# SCH_signal_16_2024-04-10.net
KiCad netlist of a schematic drawn in EasyEDA
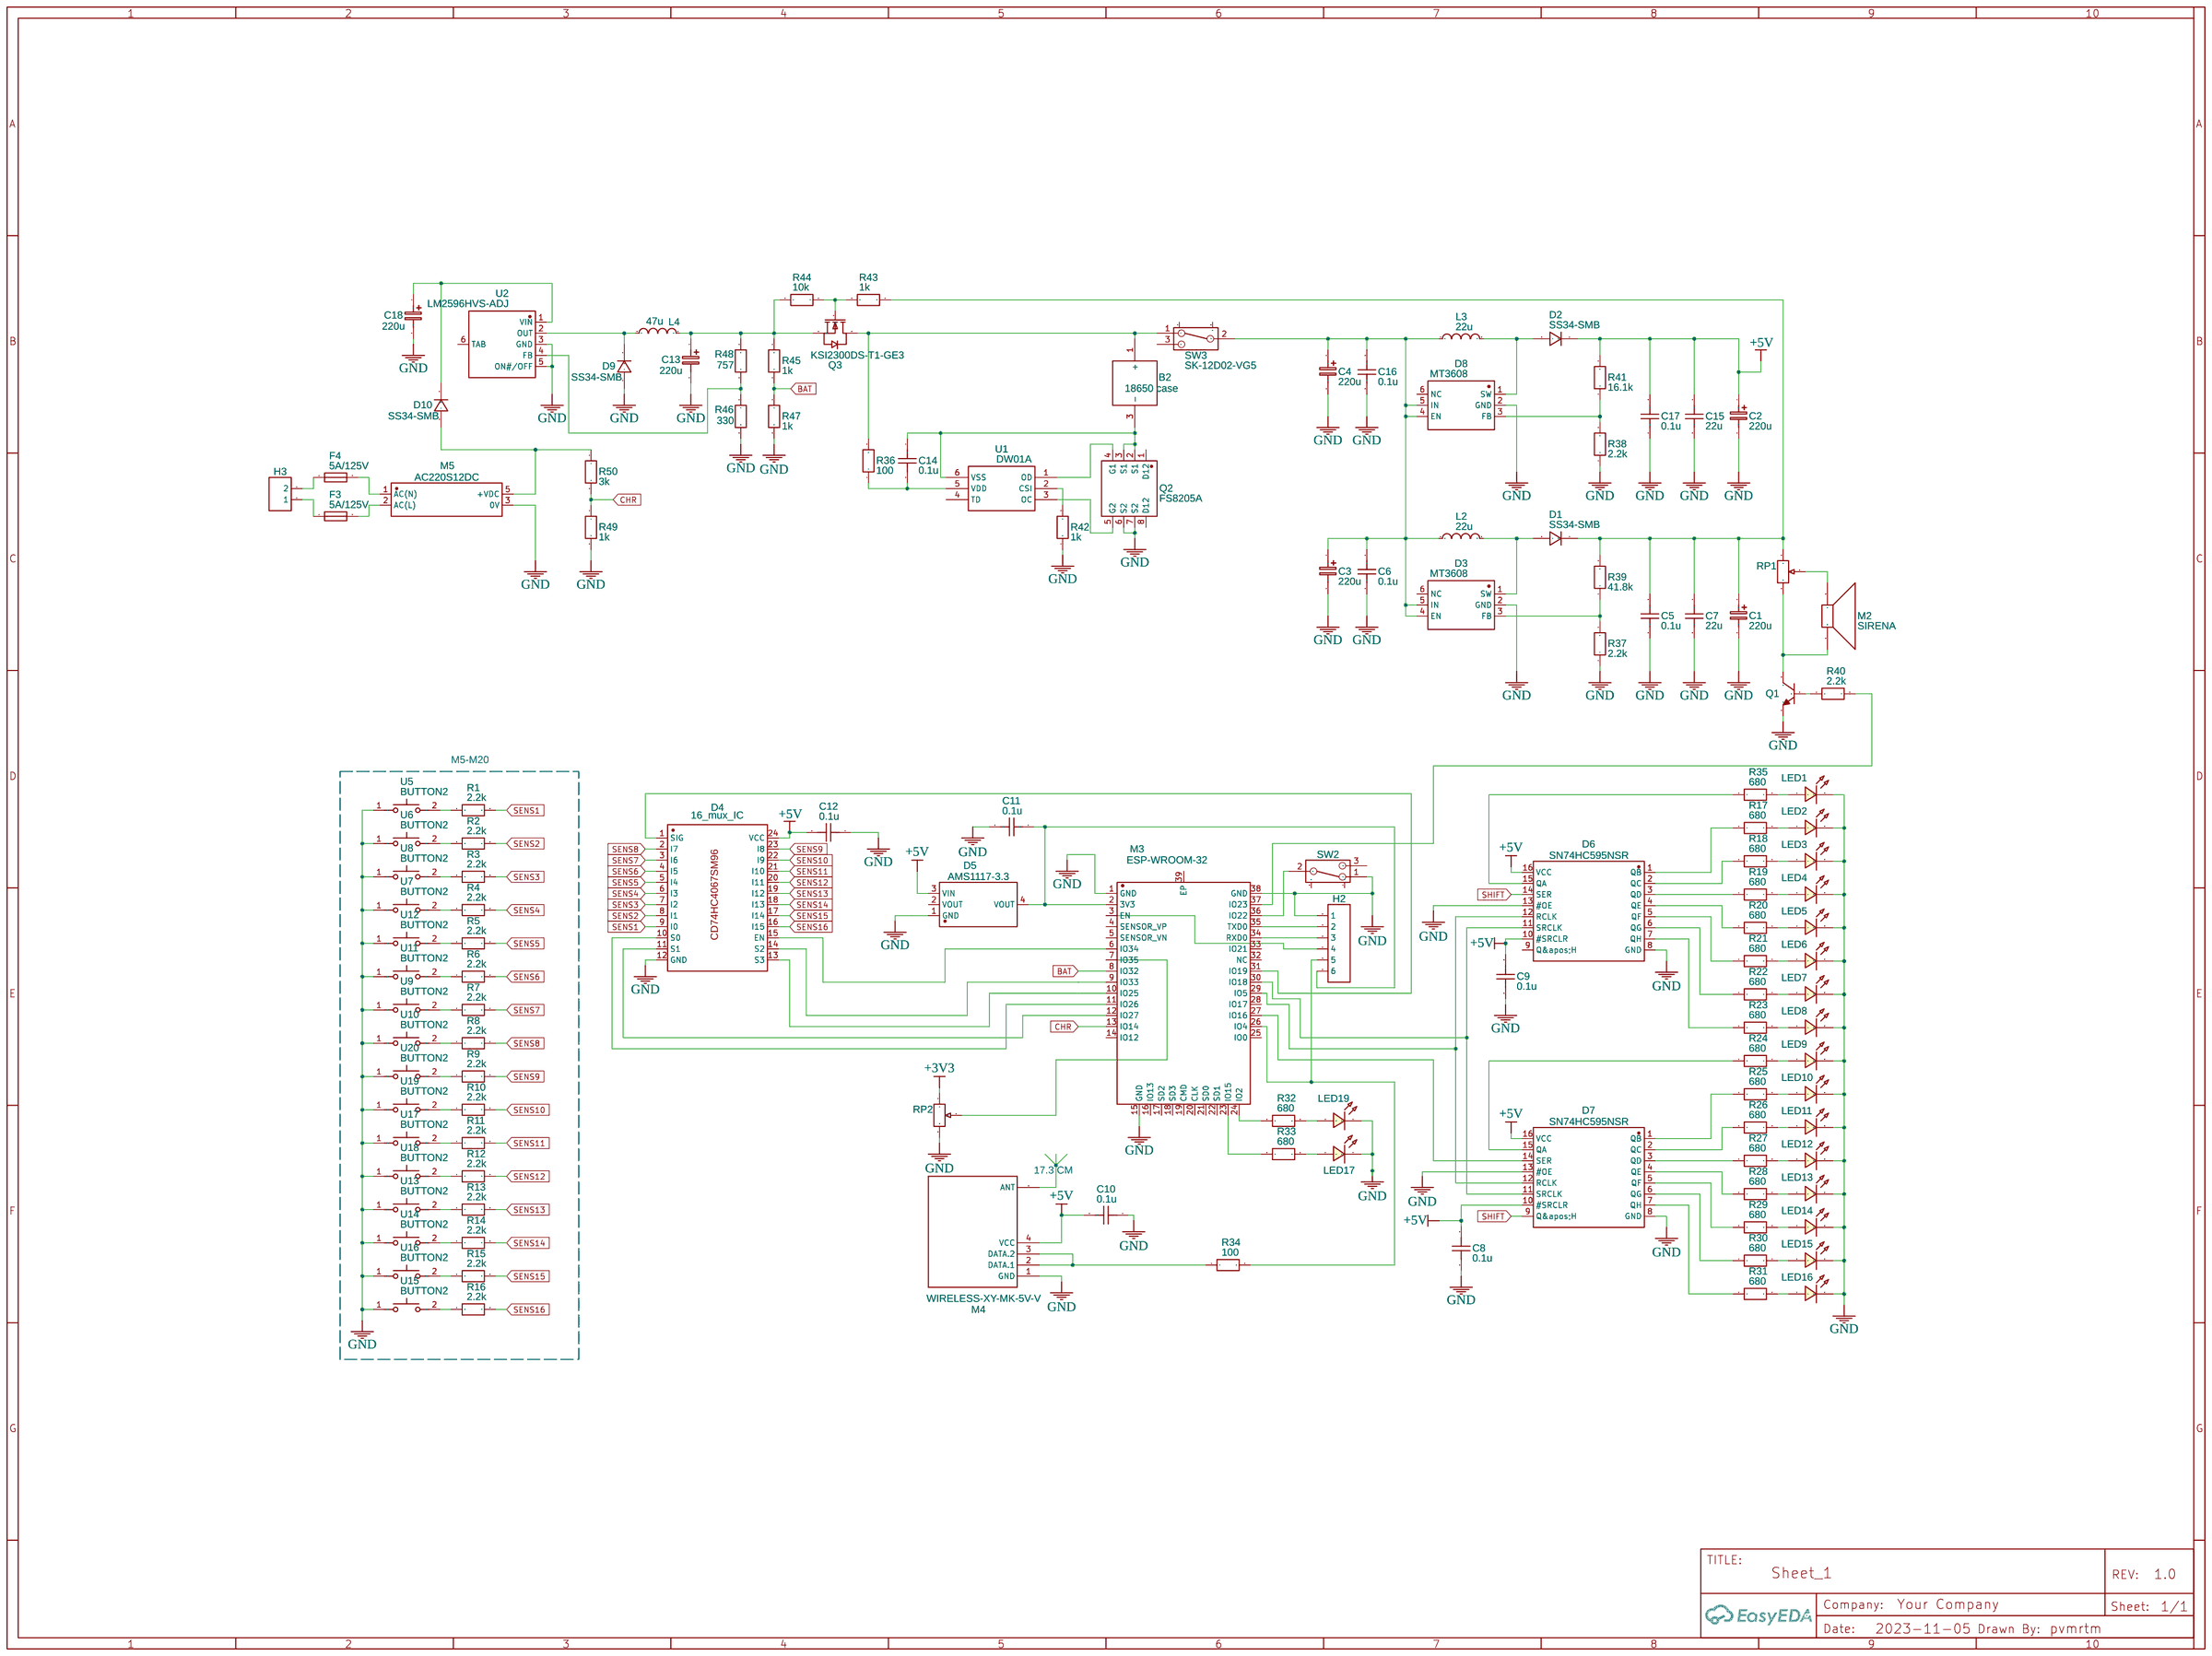
[diagram p0: schematic sheet]

(export (version "E")
  (design (tool "Eeschema 10.0.6"))
  (components
    (comp (ref "B2") (value "18650 case") (libsource (lib "") (part "18650 case")))
    (comp (ref "C1") (value "220u") (libsource (lib "") (part "CE_SMD_D8.0×H10.5_EU_1")))
    (comp (ref "C2") (value "220u") (libsource (lib "") (part "CE_SMD_D8.0×H10.5_EU_3")))
    (comp (ref "C3") (value "220u") (libsource (lib "") (part "CE_SMD_D8.0×H10.5_EU_1")))
    (comp (ref "C4") (value "220u") (libsource (lib "") (part "CE_SMD_D8.0×H10.5_EU_3")))
    (comp (ref "C5") (value "0.1u") (libsource (lib "") (part "C_0603_US")))
    (comp (ref "C6") (value "0.1u") (libsource (lib "") (part "C_0603_US")))
    (comp (ref "C7") (value "22u") (libsource (lib "") (part "C_0603_US_1")))
    (comp (ref "C8") (value "0.1u") (libsource (lib "") (part "C_0603_US")))
    (comp (ref "C9") (value "0.1u") (libsource (lib "") (part "C_0603_US")))
    (comp (ref "C10") (value "0.1u") (libsource (lib "") (part "C_0603_US_2")))
    (comp (ref "C11") (value "0.1u") (libsource (lib "") (part "C_0603_US_2")))
    (comp (ref "C12") (value "0.1u") (libsource (lib "") (part "C_0603_US_2")))
    (comp (ref "C13") (value "220u") (libsource (lib "") (part "CE_SMD_D8.0×H10.5_EU_2")))
    (comp (ref "C14") (value "0.1u") (libsource (lib "") (part "C_0603_US_1")))
    (comp (ref "C15") (value "22u") (libsource (lib "") (part "C_0603_US_1")))
    (comp (ref "C16") (value "0.1u") (libsource (lib "") (part "C_0603_US")))
    (comp (ref "C17") (value "0.1u") (libsource (lib "") (part "C_0603_US")))
    (comp (ref "C18") (value "220u") (libsource (lib "") (part "CE_SMD_D8.0×H10.5_EU")))
    (comp (ref "D1")
      (value "SS34-SMB")
      (fields (field (name "Manufacturer") "GOODWORK(固得沃克)"))
      (libsource (lib "") (part "SS34-SMB"))
    )
    (comp (ref "D2")
      (value "SS34-SMB")
      (fields (field (name "Manufacturer") "GOODWORK(固得沃克)"))
      (libsource (lib "") (part "SS34-SMB"))
    )
    (comp (ref "D3")
      (value "MT3608")
      (fields (field (name "Manufacturer") "西安航天民芯"))
      (libsource (lib "") (part "MT3608"))
    )
    (comp (ref "D4") (value "16_mux_IC") (libsource (lib "") (part "16_mux_IC")))
    (comp (ref "D5")
      (value "AMS1117-3.3")
      (fields (field (name "Manufacturer") "AMS"))
      (libsource (lib "") (part "AMS1117-3.3"))
    )
    (comp (ref "D6")
      (value "SN74HC595NSR")
      (fields (field (name "Manufacturer") "TI(德州仪器)"))
      (libsource (lib "") (part "SN74HC595NSR"))
    )
    (comp (ref "D7")
      (value "SN74HC595NSR")
      (fields (field (name "Manufacturer") "TI(德州仪器)"))
      (libsource (lib "") (part "SN74HC595NSR"))
    )
    (comp (ref "D8")
      (value "MT3608")
      (fields (field (name "Manufacturer") "西安航天民芯"))
      (libsource (lib "") (part "MT3608"))
    )
    (comp (ref "D9")
      (value "SS34-SMB")
      (fields (field (name "Manufacturer") "GOODWORK(固得沃克)"))
      (libsource (lib "") (part "SS34-SMB_1"))
    )
    (comp (ref "D10")
      (value "SS34-SMB")
      (fields (field (name "Manufacturer") "GOODWORK(固得沃克)"))
      (libsource (lib "") (part "SS34-SMB_1"))
    )
    (comp (ref "F3") (value "5A/125V") (libsource (lib "") (part "5A/125V")))
    (comp (ref "F4") (value "5A/125V") (libsource (lib "") (part "5A/125V")))
    (comp (ref "H2") (value "HDR-F-2.54_1x6") (libsource (lib "") (part "HDR-F-2.54_1x6")))
    (comp (ref "H3") (value "HDR-F-2.54_1x2") (libsource (lib "") (part "HDR-F-2.54_1x2")))
    (comp (ref "L2") (value "22u") (libsource (lib "") (part "L_AXIAL-0.6_US")))
    (comp (ref "L3") (value "22u") (libsource (lib "") (part "L_AXIAL-0.6_US")))
    (comp (ref "L4") (value "47u") (libsource (lib "") (part "L_AXIAL-0.6_US_1")))
    (comp (ref "LED1")
      (value "LED-TH-5mm_R")
      (fields
        (field (name "Manufacturer Part") "333-2SURD/S530-A3")
        (field (name "Manufacturer") "EVERLIGHT(台湾亿光)")
      )
      (libsource (lib "") (part "LED-TH-5mm_R"))
    )
    (comp (ref "LED2")
      (value "LED-TH-5mm_R")
      (fields
        (field (name "Manufacturer Part") "333-2SURD/S530-A3")
        (field (name "Manufacturer") "EVERLIGHT(台湾亿光)")
      )
      (libsource (lib "") (part "LED-TH-5mm_R"))
    )
    (comp (ref "LED3")
      (value "LED-TH-5mm_R")
      (fields
        (field (name "Manufacturer Part") "333-2SURD/S530-A3")
        (field (name "Manufacturer") "EVERLIGHT(台湾亿光)")
      )
      (libsource (lib "") (part "LED-TH-5mm_R"))
    )
    (comp (ref "LED4")
      (value "LED-TH-5mm_R")
      (fields
        (field (name "Manufacturer Part") "333-2SURD/S530-A3")
        (field (name "Manufacturer") "EVERLIGHT(台湾亿光)")
      )
      (libsource (lib "") (part "LED-TH-5mm_R"))
    )
    (comp (ref "LED5")
      (value "LED-TH-5mm_R")
      (fields
        (field (name "Manufacturer Part") "333-2SURD/S530-A3")
        (field (name "Manufacturer") "EVERLIGHT(台湾亿光)")
      )
      (libsource (lib "") (part "LED-TH-5mm_R"))
    )
    (comp (ref "LED6")
      (value "LED-TH-5mm_R")
      (fields
        (field (name "Manufacturer Part") "333-2SURD/S530-A3")
        (field (name "Manufacturer") "EVERLIGHT(台湾亿光)")
      )
      (libsource (lib "") (part "LED-TH-5mm_R"))
    )
    (comp (ref "LED7")
      (value "LED-TH-5mm_R")
      (fields
        (field (name "Manufacturer Part") "333-2SURD/S530-A3")
        (field (name "Manufacturer") "EVERLIGHT(台湾亿光)")
      )
      (libsource (lib "") (part "LED-TH-5mm_R"))
    )
    (comp (ref "LED8")
      (value "LED-TH-5mm_R")
      (fields
        (field (name "Manufacturer Part") "333-2SURD/S530-A3")
        (field (name "Manufacturer") "EVERLIGHT(台湾亿光)")
      )
      (libsource (lib "") (part "LED-TH-5mm_R"))
    )
    (comp (ref "LED9")
      (value "LED-TH-5mm_R")
      (fields
        (field (name "Manufacturer Part") "333-2SURD/S530-A3")
        (field (name "Manufacturer") "EVERLIGHT(台湾亿光)")
      )
      (libsource (lib "") (part "LED-TH-5mm_R"))
    )
    (comp (ref "LED10")
      (value "LED-TH-5mm_R")
      (fields
        (field (name "Manufacturer Part") "333-2SURD/S530-A3")
        (field (name "Manufacturer") "EVERLIGHT(台湾亿光)")
      )
      (libsource (lib "") (part "LED-TH-5mm_R"))
    )
    (comp (ref "LED11")
      (value "LED-TH-5mm_R")
      (fields
        (field (name "Manufacturer Part") "333-2SURD/S530-A3")
        (field (name "Manufacturer") "EVERLIGHT(台湾亿光)")
      )
      (libsource (lib "") (part "LED-TH-5mm_R"))
    )
    (comp (ref "LED12")
      (value "LED-TH-5mm_R")
      (fields
        (field (name "Manufacturer Part") "333-2SURD/S530-A3")
        (field (name "Manufacturer") "EVERLIGHT(台湾亿光)")
      )
      (libsource (lib "") (part "LED-TH-5mm_R"))
    )
    (comp (ref "LED13")
      (value "LED-TH-5mm_R")
      (fields
        (field (name "Manufacturer Part") "333-2SURD/S530-A3")
        (field (name "Manufacturer") "EVERLIGHT(台湾亿光)")
      )
      (libsource (lib "") (part "LED-TH-5mm_R"))
    )
    (comp (ref "LED14")
      (value "LED-TH-5mm_R")
      (fields
        (field (name "Manufacturer Part") "333-2SURD/S530-A3")
        (field (name "Manufacturer") "EVERLIGHT(台湾亿光)")
      )
      (libsource (lib "") (part "LED-TH-5mm_R"))
    )
    (comp (ref "LED15")
      (value "LED-TH-5mm_R")
      (fields
        (field (name "Manufacturer Part") "333-2SURD/S530-A3")
        (field (name "Manufacturer") "EVERLIGHT(台湾亿光)")
      )
      (libsource (lib "") (part "LED-TH-5mm_R"))
    )
    (comp (ref "LED16")
      (value "LED-TH-5mm_R")
      (fields
        (field (name "Manufacturer Part") "333-2SURD/S530-A3")
        (field (name "Manufacturer") "EVERLIGHT(台湾亿光)")
      )
      (libsource (lib "") (part "LED-TH-5mm_R"))
    )
    (comp (ref "LED17")
      (value "LED-TH-5mm_G")
      (fields
        (field (name "Manufacturer Part") "333-2SYGD/S530-E2")
        (field (name "Manufacturer") "EVERLIGHT(台湾亿光)")
      )
      (libsource (lib "") (part "LED-TH-5mm_G"))
    )
    (comp (ref "LED19") (value "LED-TH-5mm_B") (libsource (lib "") (part "LED-TH-5mm_B")))
    (comp (ref "M2") (value "SIRENA") (libsource (lib "") (part "SIRENA SIMBOL")))
    (comp (ref "M3")
      (value "ESP-WROOM-32")
      (fields
        (field (name "Manufacturer Part") "ESP32-WROOM-32")
        (field (name "Manufacturer") "ESPRESSIF(乐鑫)")
      )
      (libsource (lib "") (part "ESP-WROOM-32"))
    )
    (comp (ref "M4") (value "WIRELESS-XY-MK-5V-V") (libsource (lib "") (part "WIRELESS-XY-MK-5V-V")))
    (comp (ref "M5")
      (value "AC220S12DC")
      (fields (field (name "Manufacturer Part") "AC220S12DC-3W") (field (name "Manufacturer") "HenLv(恒率)"))
      (libsource (lib "") (part "AC220S12DC-3W_C348883"))
    )
    (comp (ref "Q1")
      (value "2N3904(SOT-23)")
      (fields (field (name "Manufacturer Part") "2n3904S-RTK/PS") (field (name "Manufacturer") "KEC"))
      (libsource (lib "") (part "2N3904(SOT-23)"))
    )
    (comp (ref "Q2")
      (value "FS8205A")
      (fields (field (name "Manufacturer") "FORTUNE(富晶)"))
      (libsource (lib "") (part "FS8205A"))
    )
    (comp (ref "Q3")
      (value "KSI2300DS-T1-GE3")
      (fields (field (name "Manufacturer") "KUU"))
      (libsource (lib "") (part "KSI2300DS-T1-GE3"))
    )
    (comp (ref "R1") (value "2.2k") (libsource (lib "") (part "R_AXIAL-0.8_EU")))
    (comp (ref "R2") (value "2.2k") (libsource (lib "") (part "R_AXIAL-0.8_EU")))
    (comp (ref "R3") (value "2.2k") (libsource (lib "") (part "R_AXIAL-0.8_EU")))
    (comp (ref "R4") (value "2.2k") (libsource (lib "") (part "R_AXIAL-0.8_EU")))
    (comp (ref "R5") (value "2.2k") (libsource (lib "") (part "R_AXIAL-0.8_EU")))
    (comp (ref "R6") (value "2.2k") (libsource (lib "") (part "R_AXIAL-0.8_EU")))
    (comp (ref "R7") (value "2.2k") (libsource (lib "") (part "R_AXIAL-0.8_EU")))
    (comp (ref "R8") (value "2.2k") (libsource (lib "") (part "R_AXIAL-0.8_EU")))
    (comp (ref "R9") (value "2.2k") (libsource (lib "") (part "R_AXIAL-0.8_EU")))
    (comp (ref "R10") (value "2.2k") (libsource (lib "") (part "R_AXIAL-0.8_EU")))
    (comp (ref "R11") (value "2.2k") (libsource (lib "") (part "R_AXIAL-0.8_EU")))
    (comp (ref "R12") (value "2.2k") (libsource (lib "") (part "R_AXIAL-0.8_EU")))
    (comp (ref "R13") (value "2.2k") (libsource (lib "") (part "R_AXIAL-0.8_EU")))
    (comp (ref "R14") (value "2.2k") (libsource (lib "") (part "R_AXIAL-0.8_EU")))
    (comp (ref "R15") (value "2.2k") (libsource (lib "") (part "R_AXIAL-0.8_EU")))
    (comp (ref "R16") (value "2.2k") (libsource (lib "") (part "R_AXIAL-0.8_EU")))
    (comp (ref "R17") (value "680") (libsource (lib "") (part "R_1206_EU_1")))
    (comp (ref "R18") (value "680") (libsource (lib "") (part "R_1206_EU_1")))
    (comp (ref "R19") (value "680") (libsource (lib "") (part "R_1206_EU_1")))
    (comp (ref "R20") (value "680") (libsource (lib "") (part "R_1206_EU_1")))
    (comp (ref "R21") (value "680") (libsource (lib "") (part "R_1206_EU_1")))
    (comp (ref "R22") (value "680") (libsource (lib "") (part "R_1206_EU_1")))
    (comp (ref "R23") (value "680") (libsource (lib "") (part "R_1206_EU_1")))
    (comp (ref "R24") (value "680") (libsource (lib "") (part "R_1206_EU_1")))
    (comp (ref "R25") (value "680") (libsource (lib "") (part "R_1206_EU_1")))
    (comp (ref "R26") (value "680") (libsource (lib "") (part "R_1206_EU_1")))
    (comp (ref "R27") (value "680") (libsource (lib "") (part "R_1206_EU_1")))
    (comp (ref "R28") (value "680") (libsource (lib "") (part "R_1206_EU_1")))
    (comp (ref "R29") (value "680") (libsource (lib "") (part "R_1206_EU_1")))
    (comp (ref "R30") (value "680") (libsource (lib "") (part "R_1206_EU_1")))
    (comp (ref "R31") (value "680") (libsource (lib "") (part "R_1206_EU_1")))
    (comp (ref "R32") (value "680") (libsource (lib "") (part "R_1206_EU_1")))
    (comp (ref "R33") (value "680") (libsource (lib "") (part "R_1206_EU_1")))
    (comp (ref "R34") (value "100") (libsource (lib "") (part "R_1206_EU_1")))
    (comp (ref "R35") (value "680") (libsource (lib "") (part "R_1206_EU_1")))
    (comp (ref "R36") (value "100") (libsource (lib "") (part "R_1206_EU")))
    (comp (ref "R37") (value "2.2k") (libsource (lib "") (part "R_1206_EU")))
    (comp (ref "R38") (value "2.2k") (libsource (lib "") (part "R_1206_EU")))
    (comp (ref "R39") (value "41.8k") (libsource (lib "") (part "R_1206_EU")))
    (comp (ref "R40") (value "2.2k") (libsource (lib "") (part "R_1206_EU_1")))
    (comp (ref "R41") (value "16.1k") (libsource (lib "") (part "R_1206_EU")))
    (comp (ref "R42") (value "1k") (libsource (lib "") (part "R_1206_EU")))
    (comp (ref "R43") (value "1k") (libsource (lib "") (part "R_1206_EU_2")))
    (comp (ref "R44") (value "10k") (libsource (lib "") (part "R_1206_EU_2")))
    (comp (ref "R45") (value "1k") (libsource (lib "") (part "R_1206_EU_3")))
    (comp (ref "R46") (value "330") (libsource (lib "") (part "R_1206_EU_3")))
    (comp (ref "R47") (value "1k") (libsource (lib "") (part "R_1206_EU_3")))
    (comp (ref "R48") (value "757") (libsource (lib "") (part "R_1206_EU_3")))
    (comp (ref "R49") (value "1k") (libsource (lib "") (part "R_1206_EU_3")))
    (comp (ref "R50") (value "3k") (libsource (lib "") (part "R_1206_EU_3")))
    (comp (ref "RP1") (value "R_3386P_EU") (libsource (lib "") (part "R_3386P_EU")))
    (comp (ref "RP2") (value "R_3386P_EU") (libsource (lib "") (part "R_3386P_EU")))
    (comp (ref "SW2")
      (value "SK-12D02-VG5")
      (fields (field (name "Manufacturer") "Rectangular Connectors - Contacts"))
      (libsource (lib "") (part "SK-12D02-VG5"))
    )
    (comp (ref "SW3")
      (value "SK-12D02-VG5")
      (fields (field (name "Manufacturer") "Rectangular Connectors - Contacts"))
      (libsource (lib "") (part "SK-12D02-VG5_1"))
    )
    (comp (ref "U1") (value "DW01A") (libsource (lib "") (part "DW01A")))
    (comp (ref "U2")
      (value "LM2596HVS-ADJ")
      (fields (field (name "Manufacturer") "UMW(友台半导体)"))
      (libsource (lib "") (part "LM2596HVS-ADJ"))
    )
    (comp (ref "U5") (value "BUTTON2") (libsource (lib "") (part "BUTTON2")))
    (comp (ref "U6") (value "BUTTON2") (libsource (lib "") (part "BUTTON2")))
    (comp (ref "U7") (value "BUTTON2") (libsource (lib "") (part "BUTTON2")))
    (comp (ref "U8") (value "BUTTON2") (libsource (lib "") (part "BUTTON2")))
    (comp (ref "U9") (value "BUTTON2") (libsource (lib "") (part "BUTTON2")))
    (comp (ref "U10") (value "BUTTON2") (libsource (lib "") (part "BUTTON2")))
    (comp (ref "U11") (value "BUTTON2") (libsource (lib "") (part "BUTTON2")))
    (comp (ref "U12") (value "BUTTON2") (libsource (lib "") (part "BUTTON2")))
    (comp (ref "U13") (value "BUTTON2") (libsource (lib "") (part "BUTTON2")))
    (comp (ref "U14") (value "BUTTON2") (libsource (lib "") (part "BUTTON2")))
    (comp (ref "U15") (value "BUTTON2") (libsource (lib "") (part "BUTTON2")))
    (comp (ref "U16") (value "BUTTON2") (libsource (lib "") (part "BUTTON2")))
    (comp (ref "U17") (value "BUTTON2") (libsource (lib "") (part "BUTTON2")))
    (comp (ref "U18") (value "BUTTON2") (libsource (lib "") (part "BUTTON2")))
    (comp (ref "U19") (value "BUTTON2") (libsource (lib "") (part "BUTTON2")))
    (comp (ref "U20") (value "BUTTON2") (libsource (lib "") (part "BUTTON2")))
  )
  (nets
    (net (code "1") (name "+3V3") (class "Default")
      (node (ref "RP2") (pin "1") (pinfunction "1_1") (pintype "input"))
    )
    (net (code "2") (name "+5V") (class "Default")
      (node (ref "C10") (pin "2") (pinfunction "2_2") (pintype "unspecified"))
      (node (ref "C12") (pin "2") (pinfunction "2_2") (pintype "unspecified"))
      (node (ref "C15") (pin "1") (pinfunction "1_1") (pintype "unspecified"))
      (node (ref "C17") (pin "2") (pinfunction "2_2") (pintype "unspecified"))
      (node (ref "C2") (pin "1") (pinfunction "1_1") (pintype "unspecified"))
      (node (ref "C8") (pin "2") (pinfunction "2_2") (pintype "unspecified"))
      (node (ref "C9") (pin "2") (pinfunction "2_2") (pintype "unspecified"))
      (node (ref "D2") (pin "1") (pinfunction "C_1") (pintype "unspecified"))
      (node (ref "D4") (pin "24") (pinfunction "VCC_24") (pintype "unspecified"))
      (node (ref "D5") (pin "3") (pinfunction "VIN_3") (pintype "unspecified"))
      (node (ref "D6") (pin "10") (pinfunction "#SRCLR_10") (pintype "unspecified"))
      (node (ref "D6") (pin "16") (pinfunction "VCC_16") (pintype "unspecified"))
      (node (ref "D7") (pin "10") (pinfunction "#SRCLR_10") (pintype "unspecified"))
      (node (ref "D7") (pin "16") (pinfunction "VCC_16") (pintype "unspecified"))
      (node (ref "M4") (pin "4") (pinfunction "VCC_4") (pintype "bidirectional"))
      (node (ref "R41") (pin "2") (pinfunction "2_2") (pintype "unspecified"))
    )
    (net (code "3") (name "BAT") (class "Default")
      (node (ref "M3") (pin "8") (pinfunction "IO32_8") (pintype "unspecified"))
      (node (ref "R45") (pin "2") (pinfunction "2_2") (pintype "unspecified"))
      (node (ref "R47") (pin "1") (pinfunction "1_1") (pintype "unspecified"))
    )
    (net (code "4") (name "CHR") (class "Default")
      (node (ref "M3") (pin "13") (pinfunction "IO14_13") (pintype "unspecified"))
      (node (ref "R49") (pin "1") (pinfunction "1_1") (pintype "unspecified"))
      (node (ref "R50") (pin "2") (pinfunction "2_2") (pintype "unspecified"))
    )
    (net (code "5") (name "GND") (class "Default")
      (node (ref "C1") (pin "2") (pinfunction "2_2") (pintype "unspecified"))
      (node (ref "C10") (pin "1") (pinfunction "1_1") (pintype "unspecified"))
      (node (ref "C11") (pin "2") (pinfunction "2_2") (pintype "unspecified"))
      (node (ref "C12") (pin "1") (pinfunction "1_1") (pintype "unspecified"))
      (node (ref "C13") (pin "2") (pinfunction "2_2") (pintype "unspecified"))
      (node (ref "C15") (pin "2") (pinfunction "2_2") (pintype "unspecified"))
      (node (ref "C16") (pin "1") (pinfunction "1_1") (pintype "unspecified"))
      (node (ref "C17") (pin "1") (pinfunction "1_1") (pintype "unspecified"))
      (node (ref "C18") (pin "2") (pinfunction "2_2") (pintype "unspecified"))
      (node (ref "C2") (pin "2") (pinfunction "2_2") (pintype "unspecified"))
      (node (ref "C3") (pin "2") (pinfunction "2_2") (pintype "unspecified"))
      (node (ref "C4") (pin "2") (pinfunction "2_2") (pintype "unspecified"))
      (node (ref "C5") (pin "1") (pinfunction "1_1") (pintype "unspecified"))
      (node (ref "C6") (pin "1") (pinfunction "1_1") (pintype "unspecified"))
      (node (ref "C7") (pin "2") (pinfunction "2_2") (pintype "unspecified"))
      (node (ref "C8") (pin "1") (pinfunction "1_1") (pintype "unspecified"))
      (node (ref "C9") (pin "1") (pinfunction "1_1") (pintype "unspecified"))
      (node (ref "D3") (pin "2") (pinfunction "GND_2") (pintype "unspecified"))
      (node (ref "D4") (pin "12") (pinfunction "GND_12") (pintype "unspecified"))
      (node (ref "D5") (pin "1") (pinfunction "GND_1") (pintype "unspecified"))
      (node (ref "D6") (pin "13") (pinfunction "#OE_13") (pintype "unspecified"))
      (node (ref "D6") (pin "8") (pinfunction "GND_8") (pintype "unspecified"))
      (node (ref "D7") (pin "13") (pinfunction "#OE_13") (pintype "unspecified"))
      (node (ref "D7") (pin "8") (pinfunction "GND_8") (pintype "unspecified"))
      (node (ref "D8") (pin "2") (pinfunction "GND_2") (pintype "unspecified"))
      (node (ref "D9") (pin "2") (pinfunction "A_2") (pintype "unspecified"))
      (node (ref "H2") (pin "1") (pinfunction "1_1") (pintype "input"))
      (node (ref "LED1") (pin "2") (pinfunction "2_2") (pintype "unspecified"))
      (node (ref "LED10") (pin "2") (pinfunction "2_2") (pintype "unspecified"))
      (node (ref "LED11") (pin "2") (pinfunction "2_2") (pintype "unspecified"))
      (node (ref "LED12") (pin "2") (pinfunction "2_2") (pintype "unspecified"))
      (node (ref "LED13") (pin "2") (pinfunction "2_2") (pintype "unspecified"))
      (node (ref "LED14") (pin "2") (pinfunction "2_2") (pintype "unspecified"))
      (node (ref "LED15") (pin "2") (pinfunction "2_2") (pintype "unspecified"))
      (node (ref "LED16") (pin "2") (pinfunction "2_2") (pintype "unspecified"))
      (node (ref "LED17") (pin "2") (pinfunction "2_2") (pintype "unspecified"))
      (node (ref "LED19") (pin "2") (pinfunction "2_2") (pintype "unspecified"))
      (node (ref "LED2") (pin "2") (pinfunction "2_2") (pintype "unspecified"))
      (node (ref "LED3") (pin "2") (pinfunction "2_2") (pintype "unspecified"))
      (node (ref "LED4") (pin "2") (pinfunction "2_2") (pintype "unspecified"))
      (node (ref "LED5") (pin "2") (pinfunction "2_2") (pintype "unspecified"))
      (node (ref "LED6") (pin "2") (pinfunction "2_2") (pintype "unspecified"))
      (node (ref "LED7") (pin "2") (pinfunction "2_2") (pintype "unspecified"))
      (node (ref "LED8") (pin "2") (pinfunction "2_2") (pintype "unspecified"))
      (node (ref "LED9") (pin "2") (pinfunction "2_2") (pintype "unspecified"))
      (node (ref "M3") (pin "1") (pinfunction "GND_1") (pintype "unspecified"))
      (node (ref "M3") (pin "15") (pinfunction "GND_15") (pintype "unspecified"))
      (node (ref "M3") (pin "38") (pinfunction "GND_38") (pintype "unspecified"))
      (node (ref "M4") (pin "1") (pinfunction "GND_1") (pintype "bidirectional"))
      (node (ref "M5") (pin "3") (pinfunction "0V_3") (pintype "unspecified"))
      (node (ref "Q1") (pin "1") (pinfunction "E_1") (pintype "input"))
      (node (ref "Q2") (pin "6") (pinfunction "S2_6") (pintype "unspecified"))
      (node (ref "Q2") (pin "7") (pinfunction "S2_7") (pintype "unspecified"))
      (node (ref "R37") (pin "1") (pinfunction "1_1") (pintype "unspecified"))
      (node (ref "R38") (pin "1") (pinfunction "1_1") (pintype "unspecified"))
      (node (ref "R42") (pin "1") (pinfunction "1_1") (pintype "unspecified"))
      (node (ref "R46") (pin "2") (pinfunction "2_2") (pintype "unspecified"))
      (node (ref "R47") (pin "2") (pinfunction "2_2") (pintype "unspecified"))
      (node (ref "R49") (pin "2") (pinfunction "2_2") (pintype "unspecified"))
      (node (ref "RP2") (pin "3") (pinfunction "3_3") (pintype "input"))
      (node (ref "SW2") (pin "1") (pinfunction "1_1") (pintype "unspecified"))
      (node (ref "U10") (pin "1") (pinfunction "1_1") (pintype "unspecified"))
      (node (ref "U11") (pin "1") (pinfunction "1_1") (pintype "unspecified"))
      (node (ref "U12") (pin "1") (pinfunction "1_1") (pintype "unspecified"))
      (node (ref "U13") (pin "1") (pinfunction "1_1") (pintype "unspecified"))
      (node (ref "U14") (pin "1") (pinfunction "1_1") (pintype "unspecified"))
      (node (ref "U15") (pin "1") (pinfunction "1_1") (pintype "unspecified"))
      (node (ref "U16") (pin "1") (pinfunction "1_1") (pintype "unspecified"))
      (node (ref "U17") (pin "1") (pinfunction "1_1") (pintype "unspecified"))
      (node (ref "U18") (pin "1") (pinfunction "1_1") (pintype "unspecified"))
      (node (ref "U19") (pin "1") (pinfunction "1_1") (pintype "unspecified"))
      (node (ref "U2") (pin "3") (pinfunction "GND_3") (pintype "unspecified"))
      (node (ref "U2") (pin "5") (pinfunction "ON#/OFF_5") (pintype "unspecified"))
      (node (ref "U20") (pin "1") (pinfunction "1_1") (pintype "unspecified"))
      (node (ref "U5") (pin "1") (pinfunction "1_1") (pintype "unspecified"))
      (node (ref "U6") (pin "1") (pinfunction "1_1") (pintype "unspecified"))
      (node (ref "U7") (pin "1") (pinfunction "1_1") (pintype "unspecified"))
      (node (ref "U8") (pin "1") (pinfunction "1_1") (pintype "unspecified"))
      (node (ref "U9") (pin "1") (pinfunction "1_1") (pintype "unspecified"))
    )
    (net (code "6") (name "Net-(B2-+)") (class "Default")
      (node (ref "B2") (pin "1") (pinfunction "+_1") (pintype "unspecified"))
      (node (ref "Q3") (pin "3") (pinfunction "D_3") (pintype "unspecified"))
      (node (ref "R36") (pin "2") (pinfunction "2_2") (pintype "unspecified"))
      (node (ref "SW3") (pin "1") (pinfunction "1_1") (pintype "unspecified"))
    )
    (net (code "7") (name "Net-(B2--)") (class "Default")
      (node (ref "B2") (pin "3") (pinfunction "-_3") (pintype "unspecified"))
      (node (ref "C14") (pin "1") (pinfunction "1_1") (pintype "unspecified"))
      (node (ref "Q2") (pin "2") (pinfunction "S1_2") (pintype "unspecified"))
      (node (ref "Q2") (pin "3") (pinfunction "S1_3") (pintype "unspecified"))
      (node (ref "U1") (pin "6") (pinfunction "VSS_6") (pintype "unspecified"))
    )
    (net (code "8") (name "Net-(D1-A)") (class "Default")
      (node (ref "D1") (pin "2") (pinfunction "A_2") (pintype "unspecified"))
      (node (ref "D3") (pin "1") (pinfunction "SW_1") (pintype "unspecified"))
      (node (ref "L2") (pin "2") (pinfunction "2_2") (pintype "unspecified"))
    )
    (net (code "9") (name "Net-(D1-C)") (class "Default")
      (node (ref "C1") (pin "1") (pinfunction "1_1") (pintype "unspecified"))
      (node (ref "C5") (pin "2") (pinfunction "2_2") (pintype "unspecified"))
      (node (ref "C7") (pin "1") (pinfunction "1_1") (pintype "unspecified"))
      (node (ref "D1") (pin "1") (pinfunction "C_1") (pintype "unspecified"))
      (node (ref "R39") (pin "2") (pinfunction "2_2") (pintype "unspecified"))
      (node (ref "R43") (pin "1") (pinfunction "1_1") (pintype "unspecified"))
      (node (ref "RP1") (pin "1") (pinfunction "1_1") (pintype "input"))
    )
    (net (code "10") (name "Net-(D2-A)") (class "Default")
      (node (ref "D2") (pin "2") (pinfunction "A_2") (pintype "unspecified"))
      (node (ref "D8") (pin "1") (pinfunction "SW_1") (pintype "unspecified"))
      (node (ref "L3") (pin "2") (pinfunction "2_2") (pintype "unspecified"))
    )
    (net (code "11") (name "Net-(D3-EN)") (class "Default")
      (node (ref "C16") (pin "2") (pinfunction "2_2") (pintype "unspecified"))
      (node (ref "C3") (pin "1") (pinfunction "1_1") (pintype "unspecified"))
      (node (ref "C4") (pin "1") (pinfunction "1_1") (pintype "unspecified"))
      (node (ref "C6") (pin "2") (pinfunction "2_2") (pintype "unspecified"))
      (node (ref "D3") (pin "4") (pinfunction "EN_4") (pintype "unspecified"))
      (node (ref "D3") (pin "5") (pinfunction "IN_5") (pintype "unspecified"))
      (node (ref "D8") (pin "4") (pinfunction "EN_4") (pintype "unspecified"))
      (node (ref "D8") (pin "5") (pinfunction "IN_5") (pintype "unspecified"))
      (node (ref "L2") (pin "1") (pinfunction "1_1") (pintype "unspecified"))
      (node (ref "L3") (pin "1") (pinfunction "1_1") (pintype "unspecified"))
      (node (ref "SW3") (pin "2") (pinfunction "2_2") (pintype "unspecified"))
    )
    (net (code "12") (name "Net-(D3-FB)") (class "Default")
      (node (ref "D3") (pin "3") (pinfunction "FB_3") (pintype "unspecified"))
      (node (ref "R37") (pin "2") (pinfunction "2_2") (pintype "unspecified"))
      (node (ref "R39") (pin "1") (pinfunction "1_1") (pintype "unspecified"))
    )
    (net (code "13") (name "Net-(D4-EN)") (class "Default")
      (node (ref "D4") (pin "15") (pinfunction "EN_15") (pintype "unspecified"))
      (node (ref "M3") (pin "6") (pinfunction "IO34_6") (pintype "unspecified"))
    )
    (net (code "14") (name "Net-(D4-S0)") (class "Default")
      (node (ref "D4") (pin "10") (pinfunction "S0_10") (pintype "unspecified"))
      (node (ref "M3") (pin "11") (pinfunction "IO26_11") (pintype "unspecified"))
    )
    (net (code "15") (name "Net-(D4-S1)") (class "Default")
      (node (ref "D4") (pin "11") (pinfunction "S1_11") (pintype "unspecified"))
      (node (ref "M3") (pin "12") (pinfunction "IO27_12") (pintype "unspecified"))
    )
    (net (code "16") (name "Net-(D4-S2)") (class "Default")
      (node (ref "D4") (pin "14") (pinfunction "S2_14") (pintype "unspecified"))
      (node (ref "M3") (pin "9") (pinfunction "IO33_9") (pintype "unspecified"))
    )
    (net (code "17") (name "Net-(D4-S3)") (class "Default")
      (node (ref "D4") (pin "13") (pinfunction "S3_13") (pintype "unspecified"))
      (node (ref "M3") (pin "10") (pinfunction "IO25_10") (pintype "unspecified"))
    )
    (net (code "18") (name "Net-(D4-SIG)") (class "Default")
      (node (ref "D4") (pin "1") (pinfunction "SIG_1") (pintype "unspecified"))
      (node (ref "M3") (pin "31") (pinfunction "IO19_31") (pintype "unspecified"))
    )
    (net (code "19") (name "Net-(D6-QA)") (class "Default")
      (node (ref "D6") (pin "15") (pinfunction "QA_15") (pintype "unspecified"))
      (node (ref "R35") (pin "1") (pinfunction "1_1") (pintype "unspecified"))
    )
    (net (code "20") (name "Net-(D6-QB)") (class "Default")
      (node (ref "D6") (pin "1") (pinfunction "QB_1") (pintype "unspecified"))
      (node (ref "R17") (pin "1") (pinfunction "1_1") (pintype "unspecified"))
    )
    (net (code "21") (name "Net-(D6-QC)") (class "Default")
      (node (ref "D6") (pin "2") (pinfunction "QC_2") (pintype "unspecified"))
      (node (ref "R18") (pin "1") (pinfunction "1_1") (pintype "unspecified"))
    )
    (net (code "22") (name "Net-(D6-QD)") (class "Default")
      (node (ref "D6") (pin "3") (pinfunction "QD_3") (pintype "unspecified"))
      (node (ref "R19") (pin "1") (pinfunction "1_1") (pintype "unspecified"))
    )
    (net (code "23") (name "Net-(D6-QE)") (class "Default")
      (node (ref "D6") (pin "4") (pinfunction "QE_4") (pintype "unspecified"))
      (node (ref "R20") (pin "1") (pinfunction "1_1") (pintype "unspecified"))
    )
    (net (code "24") (name "Net-(D6-QF)") (class "Default")
      (node (ref "D6") (pin "5") (pinfunction "QF_5") (pintype "unspecified"))
      (node (ref "R21") (pin "1") (pinfunction "1_1") (pintype "unspecified"))
    )
    (net (code "25") (name "Net-(D6-QG)") (class "Default")
      (node (ref "D6") (pin "6") (pinfunction "QG_6") (pintype "unspecified"))
      (node (ref "R22") (pin "1") (pinfunction "1_1") (pintype "unspecified"))
    )
    (net (code "26") (name "Net-(D6-QH)") (class "Default")
      (node (ref "D6") (pin "7") (pinfunction "QH_7") (pintype "unspecified"))
      (node (ref "R23") (pin "1") (pinfunction "1_1") (pintype "unspecified"))
    )
    (net (code "27") (name "Net-(D6-RCLK)") (class "Default")
      (node (ref "D6") (pin "12") (pinfunction "RCLK_12") (pintype "unspecified"))
      (node (ref "D7") (pin "12") (pinfunction "RCLK_12") (pintype "unspecified"))
      (node (ref "M3") (pin "29") (pinfunction "IO5_29") (pintype "unspecified"))
    )
    (net (code "28") (name "Net-(D6-SRCLK)") (class "Default")
      (node (ref "D6") (pin "11") (pinfunction "SRCLK_11") (pintype "unspecified"))
      (node (ref "D7") (pin "11") (pinfunction "SRCLK_11") (pintype "unspecified"))
      (node (ref "M3") (pin "30") (pinfunction "IO18_30") (pintype "unspecified"))
    )
    (net (code "29") (name "Net-(D7-QA)") (class "Default")
      (node (ref "D7") (pin "15") (pinfunction "QA_15") (pintype "unspecified"))
      (node (ref "R24") (pin "1") (pinfunction "1_1") (pintype "unspecified"))
    )
    (net (code "30") (name "Net-(D7-QB)") (class "Default")
      (node (ref "D7") (pin "1") (pinfunction "QB_1") (pintype "unspecified"))
      (node (ref "R25") (pin "1") (pinfunction "1_1") (pintype "unspecified"))
    )
    (net (code "31") (name "Net-(D7-QC)") (class "Default")
      (node (ref "D7") (pin "2") (pinfunction "QC_2") (pintype "unspecified"))
      (node (ref "R26") (pin "1") (pinfunction "1_1") (pintype "unspecified"))
    )
    (net (code "32") (name "Net-(D7-QD)") (class "Default")
      (node (ref "D7") (pin "3") (pinfunction "QD_3") (pintype "unspecified"))
      (node (ref "R27") (pin "1") (pinfunction "1_1") (pintype "unspecified"))
    )
    (net (code "33") (name "Net-(D7-QE)") (class "Default")
      (node (ref "D7") (pin "4") (pinfunction "QE_4") (pintype "unspecified"))
      (node (ref "R28") (pin "1") (pinfunction "1_1") (pintype "unspecified"))
    )
    (net (code "34") (name "Net-(D7-QF)") (class "Default")
      (node (ref "D7") (pin "5") (pinfunction "QF_5") (pintype "unspecified"))
      (node (ref "R29") (pin "1") (pinfunction "1_1") (pintype "unspecified"))
    )
    (net (code "35") (name "Net-(D7-QG)") (class "Default")
      (node (ref "D7") (pin "6") (pinfunction "QG_6") (pintype "unspecified"))
      (node (ref "R30") (pin "1") (pinfunction "1_1") (pintype "unspecified"))
    )
    (net (code "36") (name "Net-(D7-QH)") (class "Default")
      (node (ref "D7") (pin "7") (pinfunction "QH_7") (pintype "unspecified"))
      (node (ref "R31") (pin "1") (pinfunction "1_1") (pintype "unspecified"))
    )
    (net (code "37") (name "Net-(D7-SER)") (class "Default")
      (node (ref "D7") (pin "14") (pinfunction "SER_14") (pintype "unspecified"))
      (node (ref "M3") (pin "27") (pinfunction "IO16_27") (pintype "unspecified"))
    )
    (net (code "38") (name "Net-(D8-FB)") (class "Default")
      (node (ref "D8") (pin "3") (pinfunction "FB_3") (pintype "unspecified"))
      (node (ref "R38") (pin "2") (pinfunction "2_2") (pintype "unspecified"))
      (node (ref "R41") (pin "1") (pinfunction "1_1") (pintype "unspecified"))
    )
    (net (code "39") (name "Net-(D9-C)") (class "Default")
      (node (ref "D9") (pin "1") (pinfunction "C_1") (pintype "unspecified"))
      (node (ref "L4") (pin "2") (pinfunction "2_2") (pintype "unspecified"))
      (node (ref "U2") (pin "2") (pinfunction "OUT_2") (pintype "unspecified"))
    )
    (net (code "40") (name "Net-(D10-A)") (class "Default")
      (node (ref "D10") (pin "2") (pinfunction "A_2") (pintype "unspecified"))
      (node (ref "M5") (pin "5") (pinfunction "+VDC_5") (pintype "unspecified"))
      (node (ref "R50") (pin "1") (pinfunction "1_1") (pintype "unspecified"))
    )
    (net (code "41") (name "Net-(D10-C)") (class "Default")
      (node (ref "C18") (pin "1") (pinfunction "1_1") (pintype "unspecified"))
      (node (ref "D10") (pin "1") (pinfunction "C_1") (pintype "unspecified"))
      (node (ref "U2") (pin "1") (pinfunction "VIN_1") (pintype "unspecified"))
    )
    (net (code "42") (name "Net-(F3-Pad1)") (class "Default")
      (node (ref "F3") (pin "1") (pinfunction "1_1") (pintype "unspecified"))
      (node (ref "H3") (pin "1") (pinfunction "1_1") (pintype "input"))
    )
    (net (code "43") (name "Net-(F4-Pad1)") (class "Default")
      (node (ref "F4") (pin "1") (pinfunction "1_1") (pintype "unspecified"))
      (node (ref "H3") (pin "2") (pinfunction "2_2") (pintype "input"))
    )
    (net (code "44") (name "Net-(LED1-Pad1)") (class "Default")
      (node (ref "LED1") (pin "1") (pinfunction "1_1") (pintype "unspecified"))
      (node (ref "R35") (pin "2") (pinfunction "2_2") (pintype "unspecified"))
    )
    (net (code "45") (name "Net-(LED2-Pad1)") (class "Default")
      (node (ref "LED2") (pin "1") (pinfunction "1_1") (pintype "unspecified"))
      (node (ref "R17") (pin "2") (pinfunction "2_2") (pintype "unspecified"))
    )
    (net (code "46") (name "Net-(LED3-Pad1)") (class "Default")
      (node (ref "LED3") (pin "1") (pinfunction "1_1") (pintype "unspecified"))
      (node (ref "R18") (pin "2") (pinfunction "2_2") (pintype "unspecified"))
    )
    (net (code "47") (name "Net-(LED4-Pad1)") (class "Default")
      (node (ref "LED4") (pin "1") (pinfunction "1_1") (pintype "unspecified"))
      (node (ref "R19") (pin "2") (pinfunction "2_2") (pintype "unspecified"))
    )
    (net (code "48") (name "Net-(LED5-Pad1)") (class "Default")
      (node (ref "LED5") (pin "1") (pinfunction "1_1") (pintype "unspecified"))
      (node (ref "R20") (pin "2") (pinfunction "2_2") (pintype "unspecified"))
    )
    (net (code "49") (name "Net-(LED6-Pad1)") (class "Default")
      (node (ref "LED6") (pin "1") (pinfunction "1_1") (pintype "unspecified"))
      (node (ref "R21") (pin "2") (pinfunction "2_2") (pintype "unspecified"))
    )
    (net (code "50") (name "Net-(LED7-Pad1)") (class "Default")
      (node (ref "LED7") (pin "1") (pinfunction "1_1") (pintype "unspecified"))
      (node (ref "R22") (pin "2") (pinfunction "2_2") (pintype "unspecified"))
    )
    (net (code "51") (name "Net-(LED8-Pad1)") (class "Default")
      (node (ref "LED8") (pin "1") (pinfunction "1_1") (pintype "unspecified"))
      (node (ref "R23") (pin "2") (pinfunction "2_2") (pintype "unspecified"))
    )
    (net (code "52") (name "Net-(LED9-Pad1)") (class "Default")
      (node (ref "LED9") (pin "1") (pinfunction "1_1") (pintype "unspecified"))
      (node (ref "R24") (pin "2") (pinfunction "2_2") (pintype "unspecified"))
    )
    (net (code "53") (name "Net-(LED10-Pad1)") (class "Default")
      (node (ref "LED10") (pin "1") (pinfunction "1_1") (pintype "unspecified"))
      (node (ref "R25") (pin "2") (pinfunction "2_2") (pintype "unspecified"))
    )
    (net (code "54") (name "Net-(LED11-Pad1)") (class "Default")
      (node (ref "LED11") (pin "1") (pinfunction "1_1") (pintype "unspecified"))
      (node (ref "R26") (pin "2") (pinfunction "2_2") (pintype "unspecified"))
    )
    (net (code "55") (name "Net-(LED12-Pad1)") (class "Default")
      (node (ref "LED12") (pin "1") (pinfunction "1_1") (pintype "unspecified"))
      (node (ref "R27") (pin "2") (pinfunction "2_2") (pintype "unspecified"))
    )
    (net (code "56") (name "Net-(LED13-Pad1)") (class "Default")
      (node (ref "LED13") (pin "1") (pinfunction "1_1") (pintype "unspecified"))
      (node (ref "R28") (pin "2") (pinfunction "2_2") (pintype "unspecified"))
    )
    (net (code "57") (name "Net-(LED14-Pad1)") (class "Default")
      (node (ref "LED14") (pin "1") (pinfunction "1_1") (pintype "unspecified"))
      (node (ref "R29") (pin "2") (pinfunction "2_2") (pintype "unspecified"))
    )
    (net (code "58") (name "Net-(LED15-Pad1)") (class "Default")
      (node (ref "LED15") (pin "1") (pinfunction "1_1") (pintype "unspecified"))
      (node (ref "R30") (pin "2") (pinfunction "2_2") (pintype "unspecified"))
    )
    (net (code "59") (name "Net-(LED16-Pad1)") (class "Default")
      (node (ref "LED16") (pin "1") (pinfunction "1_1") (pintype "unspecified"))
      (node (ref "R31") (pin "2") (pinfunction "2_2") (pintype "unspecified"))
    )
    (net (code "60") (name "Net-(LED17-Pad1)") (class "Default")
      (node (ref "LED17") (pin "1") (pinfunction "1_1") (pintype "unspecified"))
      (node (ref "R33") (pin "2") (pinfunction "2_2") (pintype "unspecified"))
    )
    (net (code "61") (name "Net-(LED19-Pad1)") (class "Default")
      (node (ref "LED19") (pin "1") (pinfunction "1_1") (pintype "unspecified"))
      (node (ref "R32") (pin "2") (pinfunction "2_2") (pintype "unspecified"))
    )
    (net (code "62") (name "Net-(M2-Pad1)") (class "Default")
      (node (ref "M2") (pin "1") (pinfunction "1_1") (pintype "unspecified"))
      (node (ref "RP1") (pin "2") (pinfunction "2_2") (pintype "input"))
    )
    (net (code "63") (name "Net-(M3-3V3)") (class "Default")
      (node (ref "C11") (pin "1") (pinfunction "1_1") (pintype "unspecified"))
      (node (ref "D5") (pin "4") (pinfunction "VOUT_4") (pintype "unspecified"))
      (node (ref "H2") (pin "6") (pinfunction "6_6") (pintype "input"))
      (node (ref "M3") (pin "2") (pinfunction "3V3_2") (pintype "unspecified"))
    )
    (net (code "64") (name "Net-(M3-EN)") (class "Default")
      (node (ref "H2") (pin "4") (pinfunction "4_4") (pintype "input"))
      (node (ref "M3") (pin "3") (pinfunction "EN_3") (pintype "unspecified"))
    )
    (net (code "65") (name "Net-(M3-IO2)") (class "Default")
      (node (ref "M3") (pin "24") (pinfunction "IO2_24") (pintype "unspecified"))
      (node (ref "R32") (pin "1") (pinfunction "1_1") (pintype "unspecified"))
    )
    (net (code "66") (name "Net-(M3-IO4)") (class "Default")
      (node (ref "H2") (pin "5") (pinfunction "5_5") (pintype "input"))
      (node (ref "M3") (pin "26") (pinfunction "IO4_26") (pintype "unspecified"))
      (node (ref "R34") (pin "2") (pinfunction "2_2") (pintype "unspecified"))
    )
    (net (code "67") (name "Net-(M3-IO15)") (class "Default")
      (node (ref "M3") (pin "23") (pinfunction "IO15_23") (pintype "unspecified"))
      (node (ref "R33") (pin "1") (pinfunction "1_1") (pintype "unspecified"))
    )
    (net (code "68") (name "Net-(M3-IO22)") (class "Default")
      (node (ref "M3") (pin "36") (pinfunction "IO22_36") (pintype "unspecified"))
      (node (ref "SW2") (pin "2") (pinfunction "2_2") (pintype "unspecified"))
    )
    (net (code "69") (name "Net-(M3-IO23)") (class "Default")
      (node (ref "M3") (pin "37") (pinfunction "IO23_37") (pintype "unspecified"))
      (node (ref "R40") (pin "2") (pinfunction "2_2") (pintype "unspecified"))
    )
    (net (code "70") (name "Net-(M3-IO35)") (class "Default")
      (node (ref "M3") (pin "7") (pinfunction "IO35_7") (pintype "unspecified"))
      (node (ref "RP2") (pin "2") (pinfunction "2_2") (pintype "input"))
    )
    (net (code "71") (name "Net-(M3-RXD0)") (class "Default")
      (node (ref "H2") (pin "3") (pinfunction "3_3") (pintype "input"))
      (node (ref "M3") (pin "34") (pinfunction "RXD0_34") (pintype "unspecified"))
    )
    (net (code "72") (name "Net-(M3-TXD0)") (class "Default")
      (node (ref "H2") (pin "2") (pinfunction "2_2") (pintype "input"))
      (node (ref "M3") (pin "35") (pinfunction "TXD0_35") (pintype "unspecified"))
    )
    (net (code "73") (name "Net-(M4-DATA.1)") (class "Default")
      (node (ref "M4") (pin "2") (pinfunction "DATA.1_2") (pintype "bidirectional"))
      (node (ref "M4") (pin "3") (pinfunction "DATA.2_3") (pintype "bidirectional"))
      (node (ref "R34") (pin "1") (pinfunction "1_1") (pintype "unspecified"))
    )
    (net (code "74") (name "Net-(M5-AC(L))") (class "Default")
      (node (ref "F3") (pin "2") (pinfunction "2_2") (pintype "unspecified"))
      (node (ref "M5") (pin "2") (pinfunction "AC(L)_2") (pintype "unspecified"))
    )
    (net (code "75") (name "Net-(M5-AC(N))") (class "Default")
      (node (ref "F4") (pin "2") (pinfunction "2_2") (pintype "unspecified"))
      (node (ref "M5") (pin "1") (pinfunction "AC(N)_1") (pintype "unspecified"))
    )
    (net (code "76") (name "Net-(Q1-B)") (class "Default")
      (node (ref "Q1") (pin "2") (pinfunction "B_2") (pintype "input"))
      (node (ref "R40") (pin "1") (pinfunction "1_1") (pintype "unspecified"))
    )
    (net (code "77") (name "Net-(Q1-C)") (class "Default")
      (node (ref "M2") (pin "2") (pinfunction "2_2") (pintype "unspecified"))
      (node (ref "Q1") (pin "3") (pinfunction "C_3") (pintype "input"))
      (node (ref "RP1") (pin "3") (pinfunction "3_3") (pintype "input"))
    )
    (net (code "78") (name "Net-(Q2-G1)") (class "Default")
      (node (ref "Q2") (pin "4") (pinfunction "G1_4") (pintype "unspecified"))
      (node (ref "U1") (pin "1") (pinfunction "OD_1") (pintype "unspecified"))
    )
    (net (code "79") (name "Net-(Q2-G2)") (class "Default")
      (node (ref "Q2") (pin "5") (pinfunction "G2_5") (pintype "unspecified"))
      (node (ref "U1") (pin "3") (pinfunction "OC_3") (pintype "unspecified"))
    )
    (net (code "80") (name "Net-(Q3-G)") (class "Default")
      (node (ref "Q3") (pin "1") (pinfunction "G_1") (pintype "unspecified"))
      (node (ref "R43") (pin "2") (pinfunction "2_2") (pintype "unspecified"))
      (node (ref "R44") (pin "1") (pinfunction "1_1") (pintype "unspecified"))
    )
    (net (code "81") (name "Net-(Q3-S)") (class "Default")
      (node (ref "C13") (pin "1") (pinfunction "1_1") (pintype "unspecified"))
      (node (ref "L4") (pin "1") (pinfunction "1_1") (pintype "unspecified"))
      (node (ref "Q3") (pin "2") (pinfunction "S_2") (pintype "unspecified"))
      (node (ref "R44") (pin "2") (pinfunction "2_2") (pintype "unspecified"))
      (node (ref "R45") (pin "1") (pinfunction "1_1") (pintype "unspecified"))
      (node (ref "R48") (pin "1") (pinfunction "1_1") (pintype "unspecified"))
    )
    (net (code "82") (name "Net-(R1-Pad1)") (class "Default")
      (node (ref "R1") (pin "1") (pinfunction "1_1") (pintype "unspecified"))
      (node (ref "U5") (pin "2") (pinfunction "2_2") (pintype "unspecified"))
    )
    (net (code "83") (name "Net-(R2-Pad1)") (class "Default")
      (node (ref "R2") (pin "1") (pinfunction "1_1") (pintype "unspecified"))
      (node (ref "U6") (pin "2") (pinfunction "2_2") (pintype "unspecified"))
    )
    (net (code "84") (name "Net-(R3-Pad1)") (class "Default")
      (node (ref "R3") (pin "1") (pinfunction "1_1") (pintype "unspecified"))
      (node (ref "U8") (pin "2") (pinfunction "2_2") (pintype "unspecified"))
    )
    (net (code "85") (name "Net-(R4-Pad1)") (class "Default")
      (node (ref "R4") (pin "1") (pinfunction "1_1") (pintype "unspecified"))
      (node (ref "U7") (pin "2") (pinfunction "2_2") (pintype "unspecified"))
    )
    (net (code "86") (name "Net-(R5-Pad1)") (class "Default")
      (node (ref "R5") (pin "1") (pinfunction "1_1") (pintype "unspecified"))
      (node (ref "U12") (pin "2") (pinfunction "2_2") (pintype "unspecified"))
    )
    (net (code "87") (name "Net-(R6-Pad1)") (class "Default")
      (node (ref "R6") (pin "1") (pinfunction "1_1") (pintype "unspecified"))
      (node (ref "U11") (pin "2") (pinfunction "2_2") (pintype "unspecified"))
    )
    (net (code "88") (name "Net-(R7-Pad1)") (class "Default")
      (node (ref "R7") (pin "1") (pinfunction "1_1") (pintype "unspecified"))
      (node (ref "U9") (pin "2") (pinfunction "2_2") (pintype "unspecified"))
    )
    (net (code "89") (name "Net-(R8-Pad1)") (class "Default")
      (node (ref "R8") (pin "1") (pinfunction "1_1") (pintype "unspecified"))
      (node (ref "U10") (pin "2") (pinfunction "2_2") (pintype "unspecified"))
    )
    (net (code "90") (name "Net-(R9-Pad1)") (class "Default")
      (node (ref "R9") (pin "1") (pinfunction "1_1") (pintype "unspecified"))
      (node (ref "U20") (pin "2") (pinfunction "2_2") (pintype "unspecified"))
    )
    (net (code "91") (name "Net-(R10-Pad1)") (class "Default")
      (node (ref "R10") (pin "1") (pinfunction "1_1") (pintype "unspecified"))
      (node (ref "U19") (pin "2") (pinfunction "2_2") (pintype "unspecified"))
    )
    (net (code "92") (name "Net-(R11-Pad1)") (class "Default")
      (node (ref "R11") (pin "1") (pinfunction "1_1") (pintype "unspecified"))
      (node (ref "U17") (pin "2") (pinfunction "2_2") (pintype "unspecified"))
    )
    (net (code "93") (name "Net-(R12-Pad1)") (class "Default")
      (node (ref "R12") (pin "1") (pinfunction "1_1") (pintype "unspecified"))
      (node (ref "U18") (pin "2") (pinfunction "2_2") (pintype "unspecified"))
    )
    (net (code "94") (name "Net-(R13-Pad1)") (class "Default")
      (node (ref "R13") (pin "1") (pinfunction "1_1") (pintype "unspecified"))
      (node (ref "U13") (pin "2") (pinfunction "2_2") (pintype "unspecified"))
    )
    (net (code "95") (name "Net-(R14-Pad1)") (class "Default")
      (node (ref "R14") (pin "1") (pinfunction "1_1") (pintype "unspecified"))
      (node (ref "U14") (pin "2") (pinfunction "2_2") (pintype "unspecified"))
    )
    (net (code "96") (name "Net-(R15-Pad1)") (class "Default")
      (node (ref "R15") (pin "1") (pinfunction "1_1") (pintype "unspecified"))
      (node (ref "U16") (pin "2") (pinfunction "2_2") (pintype "unspecified"))
    )
    (net (code "97") (name "Net-(R16-Pad1)") (class "Default")
      (node (ref "R16") (pin "1") (pinfunction "1_1") (pintype "unspecified"))
      (node (ref "U15") (pin "2") (pinfunction "2_2") (pintype "unspecified"))
    )
    (net (code "98") (name "Net-(U1-CSI)") (class "Default")
      (node (ref "R42") (pin "2") (pinfunction "2_2") (pintype "unspecified"))
      (node (ref "U1") (pin "2") (pinfunction "CSI_2") (pintype "unspecified"))
    )
    (net (code "99") (name "Net-(U1-VDD)") (class "Default")
      (node (ref "C14") (pin "2") (pinfunction "2_2") (pintype "unspecified"))
      (node (ref "R36") (pin "1") (pinfunction "1_1") (pintype "unspecified"))
      (node (ref "U1") (pin "5") (pinfunction "VDD_5") (pintype "unspecified"))
    )
    (net (code "100") (name "Net-(U2-FB)") (class "Default")
      (node (ref "R46") (pin "1") (pinfunction "1_1") (pintype "unspecified"))
      (node (ref "R48") (pin "2") (pinfunction "2_2") (pintype "unspecified"))
      (node (ref "U2") (pin "4") (pinfunction "FB_4") (pintype "unspecified"))
    )
    (net (code "101") (name "SENS1") (class "Default")
      (node (ref "D4") (pin "9") (pinfunction "I0_9") (pintype "unspecified"))
      (node (ref "R1") (pin "2") (pinfunction "2_2") (pintype "unspecified"))
    )
    (net (code "102") (name "SENS2") (class "Default")
      (node (ref "D4") (pin "8") (pinfunction "I1_8") (pintype "unspecified"))
      (node (ref "R2") (pin "2") (pinfunction "2_2") (pintype "unspecified"))
    )
    (net (code "103") (name "SENS3") (class "Default")
      (node (ref "D4") (pin "7") (pinfunction "I2_7") (pintype "unspecified"))
      (node (ref "R3") (pin "2") (pinfunction "2_2") (pintype "unspecified"))
    )
    (net (code "104") (name "SENS4") (class "Default")
      (node (ref "D4") (pin "6") (pinfunction "I3_6") (pintype "unspecified"))
      (node (ref "R4") (pin "2") (pinfunction "2_2") (pintype "unspecified"))
    )
    (net (code "105") (name "SENS5") (class "Default")
      (node (ref "D4") (pin "5") (pinfunction "I4_5") (pintype "unspecified"))
      (node (ref "R5") (pin "2") (pinfunction "2_2") (pintype "unspecified"))
    )
    (net (code "106") (name "SENS6") (class "Default")
      (node (ref "D4") (pin "4") (pinfunction "I5_4") (pintype "unspecified"))
      (node (ref "R6") (pin "2") (pinfunction "2_2") (pintype "unspecified"))
    )
    (net (code "107") (name "SENS7") (class "Default")
      (node (ref "D4") (pin "3") (pinfunction "I6_3") (pintype "unspecified"))
      (node (ref "R7") (pin "2") (pinfunction "2_2") (pintype "unspecified"))
    )
    (net (code "108") (name "SENS8") (class "Default")
      (node (ref "D4") (pin "2") (pinfunction "I7_2") (pintype "unspecified"))
      (node (ref "R8") (pin "2") (pinfunction "2_2") (pintype "unspecified"))
    )
    (net (code "109") (name "SENS9") (class "Default")
      (node (ref "D4") (pin "23") (pinfunction "I8_23") (pintype "unspecified"))
      (node (ref "R9") (pin "2") (pinfunction "2_2") (pintype "unspecified"))
    )
    (net (code "110") (name "SENS10") (class "Default")
      (node (ref "D4") (pin "22") (pinfunction "I9_22") (pintype "unspecified"))
      (node (ref "R10") (pin "2") (pinfunction "2_2") (pintype "unspecified"))
    )
    (net (code "111") (name "SENS11") (class "Default")
      (node (ref "D4") (pin "21") (pinfunction "I10_21") (pintype "unspecified"))
      (node (ref "R11") (pin "2") (pinfunction "2_2") (pintype "unspecified"))
    )
    (net (code "112") (name "SENS12") (class "Default")
      (node (ref "D4") (pin "20") (pinfunction "I11_20") (pintype "unspecified"))
      (node (ref "R12") (pin "2") (pinfunction "2_2") (pintype "unspecified"))
    )
    (net (code "113") (name "SENS13") (class "Default")
      (node (ref "D4") (pin "19") (pinfunction "I12_19") (pintype "unspecified"))
      (node (ref "R13") (pin "2") (pinfunction "2_2") (pintype "unspecified"))
    )
    (net (code "114") (name "SENS14") (class "Default")
      (node (ref "D4") (pin "18") (pinfunction "I13_18") (pintype "unspecified"))
      (node (ref "R14") (pin "2") (pinfunction "2_2") (pintype "unspecified"))
    )
    (net (code "115") (name "SENS15") (class "Default")
      (node (ref "D4") (pin "17") (pinfunction "I14_17") (pintype "unspecified"))
      (node (ref "R15") (pin "2") (pinfunction "2_2") (pintype "unspecified"))
    )
    (net (code "116") (name "SENS16") (class "Default")
      (node (ref "D4") (pin "16") (pinfunction "I15_16") (pintype "unspecified"))
      (node (ref "R16") (pin "2") (pinfunction "2_2") (pintype "unspecified"))
    )
    (net (code "117") (name "SHIFT") (class "Default")
      (node (ref "D6") (pin "14") (pinfunction "SER_14") (pintype "unspecified"))
      (node (ref "D7") (pin "9") (pinfunction "Q&apos;H_9") (pintype "unspecified"))
    )
    (net (code "118") (name "unconnected-(D3-NC-Pad6)") (class "Default")
      (node (ref "D3") (pin "6") (pinfunction "NC_6") (pintype "unspecified"))
    )
    (net (code "119") (name "unconnected-(D5-VOUT-Pad2)") (class "Default")
      (node (ref "D5") (pin "2") (pinfunction "VOUT_2") (pintype "unspecified"))
    )
    (net (code "120") (name "unconnected-(D6-Q&apos;H-Pad9)") (class "Default")
      (node (ref "D6") (pin "9") (pinfunction "Q&apos;H_9") (pintype "unspecified"))
    )
    (net (code "121") (name "unconnected-(D8-NC-Pad6)") (class "Default")
      (node (ref "D8") (pin "6") (pinfunction "NC_6") (pintype "unspecified"))
    )
    (net (code "122") (name "unconnected-(M3-CLK-Pad20)") (class "Default")
      (node (ref "M3") (pin "20") (pinfunction "CLK_20") (pintype "unspecified"))
    )
    (net (code "123") (name "unconnected-(M3-CMD-Pad19)") (class "Default")
      (node (ref "M3") (pin "19") (pinfunction "CMD_19") (pintype "unspecified"))
    )
    (net (code "124") (name "unconnected-(M3-EP-Pad39)") (class "Default")
      (node (ref "M3") (pin "39") (pinfunction "EP_39") (pintype "unspecified"))
    )
    (net (code "125") (name "unconnected-(M3-IO0-Pad25)") (class "Default")
      (node (ref "M3") (pin "25") (pinfunction "IO0_25") (pintype "unspecified"))
    )
    (net (code "126") (name "unconnected-(M3-IO12-Pad14)") (class "Default")
      (node (ref "M3") (pin "14") (pinfunction "IO12_14") (pintype "unspecified"))
    )
    (net (code "127") (name "unconnected-(M3-IO13-Pad16)") (class "Default")
      (node (ref "M3") (pin "16") (pinfunction "IO13_16") (pintype "unspecified"))
    )
    (net (code "128") (name "unconnected-(M3-IO17-Pad28)") (class "Default")
      (node (ref "M3") (pin "28") (pinfunction "IO17_28") (pintype "unspecified"))
    )
    (net (code "129") (name "unconnected-(M3-IO21-Pad33)") (class "Default")
      (node (ref "M3") (pin "33") (pinfunction "IO21_33") (pintype "unspecified"))
    )
    (net (code "130") (name "unconnected-(M3-NC-Pad32)") (class "Default")
      (node (ref "M3") (pin "32") (pinfunction "NC_32") (pintype "unspecified"))
    )
    (net (code "131") (name "unconnected-(M3-SD0-Pad21)") (class "Default")
      (node (ref "M3") (pin "21") (pinfunction "SD0_21") (pintype "unspecified"))
    )
    (net (code "132") (name "unconnected-(M3-SD1-Pad22)") (class "Default")
      (node (ref "M3") (pin "22") (pinfunction "SD1_22") (pintype "unspecified"))
    )
    (net (code "133") (name "unconnected-(M3-SD2-Pad17)") (class "Default")
      (node (ref "M3") (pin "17") (pinfunction "SD2_17") (pintype "unspecified"))
    )
    (net (code "134") (name "unconnected-(M3-SD3-Pad18)") (class "Default")
      (node (ref "M3") (pin "18") (pinfunction "SD3_18") (pintype "unspecified"))
    )
    (net (code "135") (name "unconnected-(M3-SENSOR_VN-Pad5)") (class "Default")
      (node (ref "M3") (pin "5") (pinfunction "SENSOR_VN_5") (pintype "unspecified"))
    )
    (net (code "136") (name "unconnected-(M3-SENSOR_VP-Pad4)") (class "Default")
      (node (ref "M3") (pin "4") (pinfunction "SENSOR_VP_4") (pintype "unspecified"))
    )
    (net (code "137") (name "unconnected-(M4-PadANT)") (class "Default")
      (node (ref "M4") (pin "ANT") (pinfunction "ANT_ANT") (pintype "bidirectional"))
    )
    (net (code "138") (name "unconnected-(Q2-D12-Pad1)") (class "Default")
      (node (ref "Q2") (pin "1") (pinfunction "D12_1") (pintype "unspecified"))
    )
    (net (code "139") (name "unconnected-(Q2-D12-Pad8)") (class "Default")
      (node (ref "Q2") (pin "8") (pinfunction "D12_8") (pintype "unspecified"))
    )
    (net (code "140") (name "unconnected-(SW2-Pad3)") (class "Default")
      (node (ref "SW2") (pin "3") (pinfunction "3_3") (pintype "unspecified"))
    )
    (net (code "141") (name "unconnected-(SW2-Pad4)") (class "Default")
      (node (ref "SW2") (pin "4") (pinfunction "4_4") (pintype "unspecified"))
    )
    (net (code "142") (name "unconnected-(SW2-Pad5)") (class "Default")
      (node (ref "SW2") (pin "5") (pinfunction "5_5") (pintype "unspecified"))
    )
    (net (code "143") (name "unconnected-(SW3-Pad3)") (class "Default")
      (node (ref "SW3") (pin "3") (pinfunction "3_3") (pintype "unspecified"))
    )
    (net (code "144") (name "unconnected-(SW3-Pad4)") (class "Default")
      (node (ref "SW3") (pin "4") (pinfunction "4_4") (pintype "unspecified"))
    )
    (net (code "145") (name "unconnected-(SW3-Pad5)") (class "Default")
      (node (ref "SW3") (pin "5") (pinfunction "5_5") (pintype "unspecified"))
    )
    (net (code "146") (name "unconnected-(U1-TD-Pad4)") (class "Default")
      (node (ref "U1") (pin "4") (pinfunction "TD_4") (pintype "unspecified"))
    )
    (net (code "147") (name "unconnected-(U2-TAB-Pad6)") (class "Default")
      (node (ref "U2") (pin "6") (pinfunction "TAB_6") (pintype "unspecified"))
    )
  )
)
